# Digital_Isolation.net
KiCad netlist of a schematic drawn in Altium Designer
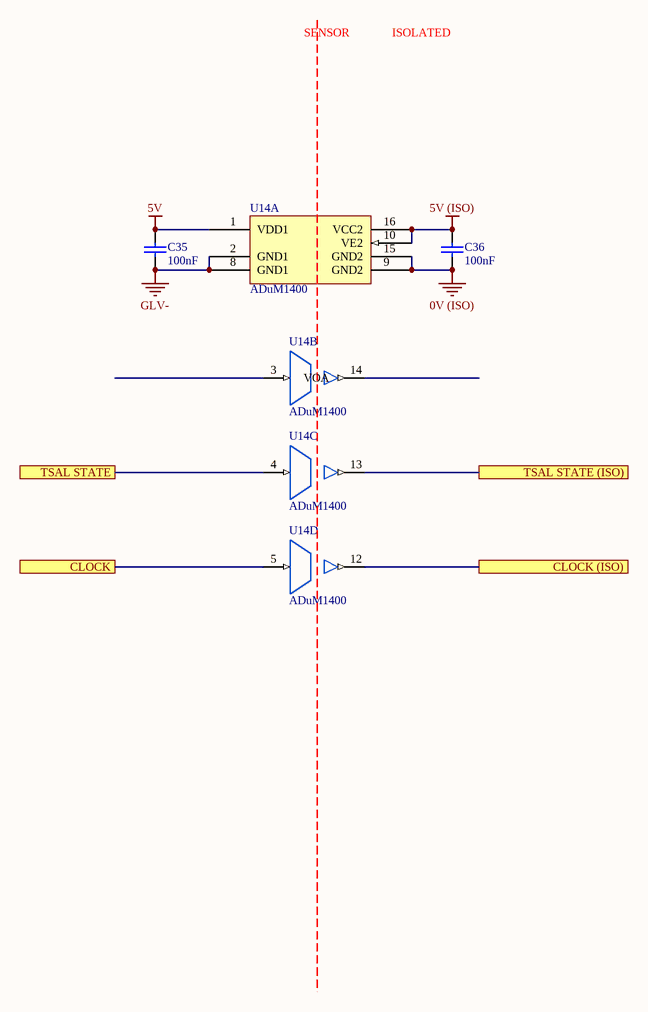
[diagram p0: Digital Isolation.SchDoc]

(export (version "E")
  (design (tool "Eeschema 10.0.6"))
  (components
    (comp (ref "C35")
      (value "100nF")
      (footprint "0805")
      (fields
        (field (name "PART NUMBER") "GCM21BR71E104KA37L")
        (field (name "TOLERANCE") "10%")
        (field (name "MANUFACTURER") "muRata")
      )
      (libsource (lib "ts_20-standard-library") (part "Capacitor"))
    )
    (comp (ref "C36")
      (value "100nF")
      (footprint "0805")
      (fields
        (field (name "PART NUMBER") "GCM21BR71E104KA37L")
        (field (name "TOLERANCE") "10%")
        (field (name "MANUFACTURER") "muRata")
      )
      (libsource (lib "ts_20-standard-library") (part "Capacitor"))
    )
    (comp (ref "U14")
      (value "ADuM1400")
      (footprint "AD 16-SOIC")
      (fields
        (field (name "MANUFACTURER") "Analog Devices")
        (field (name "DIGIKEY PART NUMBER") "ADUM1400WSRWZ-ND")
      )
      (libsource (lib "ts_20-standard-library") (part "ADuM1400"))
    )
  )
  (nets
    (net (code "1") (name "/CLOCK") (class "Default")
      (node (ref "U14") (pin "5") (pinfunction "VIC_5") (pintype "input"))
    )
    (net (code "2") (name "/CLOCK (ISO)") (class "Default")
      (node (ref "U14") (pin "12") (pinfunction "VOC_12") (pintype "output"))
    )
    (net (code "3") (name "/TSAL STATE") (class "Default")
      (node (ref "U14") (pin "4") (pinfunction "VIB_4") (pintype "input"))
    )
    (net (code "4") (name "/TSAL STATE (ISO)") (class "Default")
      (node (ref "U14") (pin "13") (pinfunction "VOB_13") (pintype "output"))
    )
    (net (code "5") (name "0V (ISO)") (class "Default")
      (node (ref "C36") (pin "1") (pinfunction "1_1") (pintype "passive"))
      (node (ref "U14") (pin "15") (pinfunction "GND2_15") (pintype "power_in"))
      (node (ref "U14") (pin "9") (pinfunction "GND2_9") (pintype "power_in"))
    )
    (net (code "6") (name "5V") (class "Default")
      (node (ref "C35") (pin "2") (pinfunction "2_2") (pintype "passive"))
      (node (ref "U14") (pin "1") (pinfunction "VDD1_1") (pintype "power_in"))
    )
    (net (code "7") (name "5V (ISO)") (class "Default")
      (node (ref "C36") (pin "2") (pinfunction "2_2") (pintype "passive"))
      (node (ref "U14") (pin "10") (pinfunction "VE2_10") (pintype "input"))
      (node (ref "U14") (pin "16") (pinfunction "VCC2_16") (pintype "power_in"))
    )
    (net (code "8") (name "GLV-") (class "Default")
      (node (ref "C35") (pin "1") (pinfunction "1_1") (pintype "passive"))
      (node (ref "U14") (pin "2") (pinfunction "GND1_2") (pintype "power_in"))
      (node (ref "U14") (pin "8") (pinfunction "GND1_8") (pintype "power_in"))
    )
    (net (code "9") (name "unconnected-(U14B-VIA-Pad3)") (class "Default")
      (node (ref "U14") (pin "3") (pinfunction "VIA_3") (pintype "input"))
    )
    (net (code "10") (name "unconnected-(U14B-VOA-Pad14)") (class "Default")
      (node (ref "U14") (pin "14") (pinfunction "VOA_14") (pintype "output"))
    )
  )
)
